# Accelerometer.net
KiCad netlist of a schematic drawn in Altium Designer
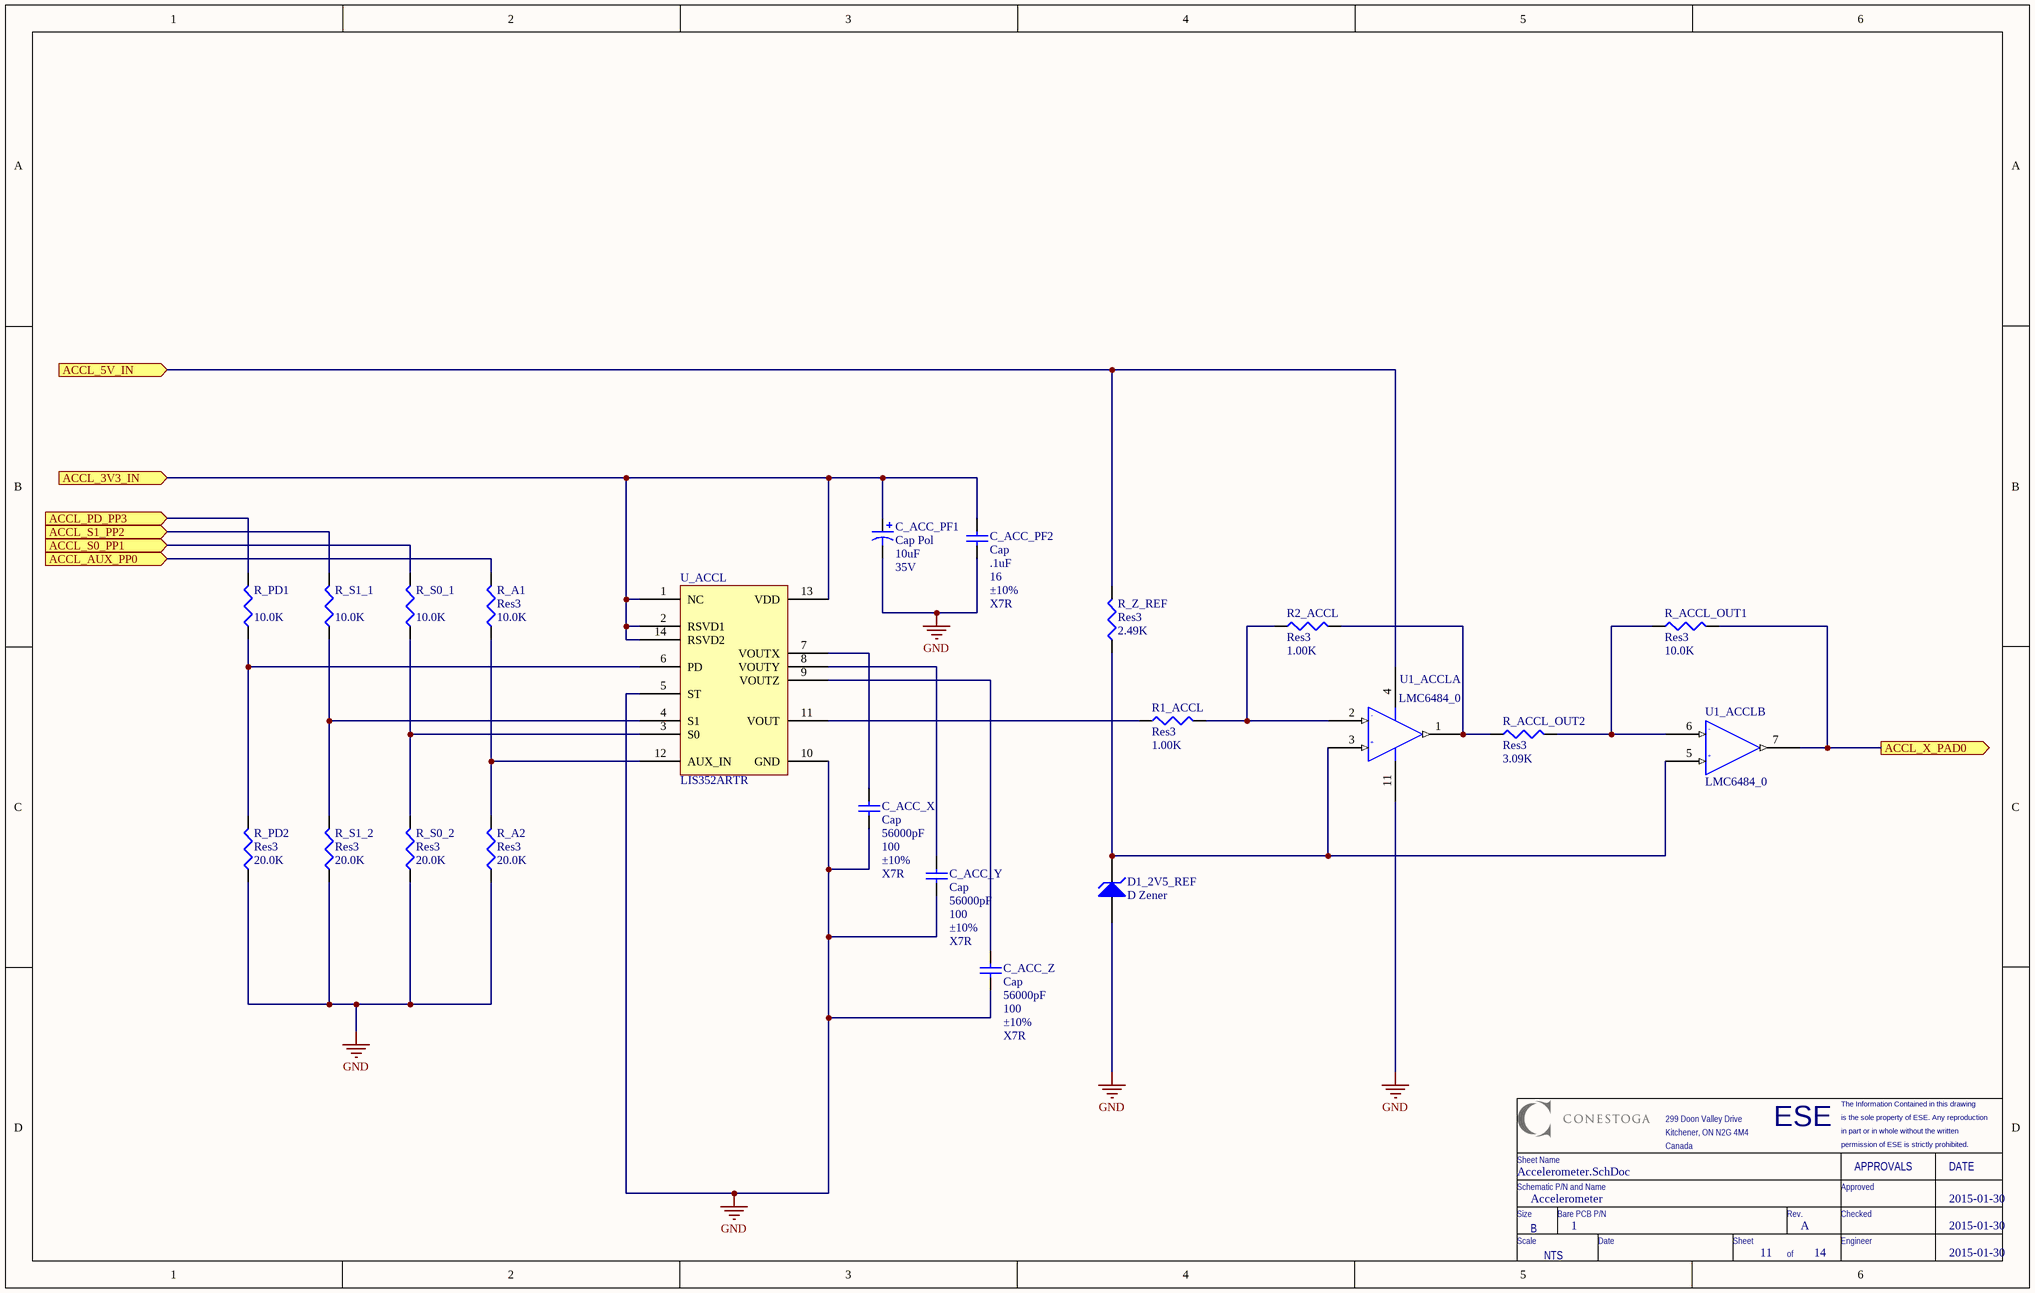
[diagram p0: Accelerometer.SchDoc]

(export (version "E")
  (design (tool "Eeschema 10.0.6"))
  (components
    (comp (ref "C_ACC_PF1")
      (value "Cap Pol")
      (footprint "CAPACITOR_5MM")
      (description "CAP 85C 10uF ±20% 35V WX Series Aluminum Electrolytic")
      (fields
        (field (name "ALTIUM_VALUE") "10uF")
        (field (name "VOLTAGE") "35V")
        (field (name "MPN") "UWX1V100MCL1GB")
      )
      (libsource (lib "esd_library") (part "Cap Polar-10uF-35V"))
    )
    (comp (ref "C_ACC_PF2")
      (value "Cap")
      (footprint "CAPC2012X09M")
      (description "CAP CER .1uF 16v X7R 0805")
      (fields
        (field (name "ALTIUM_VALUE") ".1uF")
        (field (name "WV") "16")
        (field (name "TOLERANCE") "±10%")
        (field (name "TYPE") "X7R")
        (field (name "MPN") "C0805C104K4RACTU")
      )
      (libsource (lib "esd_library") (part "CAP-X7R-.1uF-16V-±10%"))
    )
    (comp (ref "C_ACC_X")
      (value "Cap")
      (footprint "CAPC2012X09M")
      (description "CAP CER 56000pF 100v X7R 0805")
      (fields
        (field (name "ALTIUM_VALUE") "56000pF")
        (field (name "WV") "100")
        (field (name "TOLERANCE") "±10%")
        (field (name "TYPE") "X7R")
        (field (name "MPN") "C0805C563K1RACTU")
      )
      (libsource (lib "esd_library") (part "CAP-X7R-56000pF-100V-±10%"))
    )
    (comp (ref "C_ACC_Y")
      (value "Cap")
      (footprint "CAPC2012X09M")
      (description "CAP CER 56000pF 100v X7R 0805")
      (fields
        (field (name "ALTIUM_VALUE") "56000pF")
        (field (name "WV") "100")
        (field (name "TOLERANCE") "±10%")
        (field (name "TYPE") "X7R")
        (field (name "MPN") "C0805C563K1RACTU")
      )
      (libsource (lib "esd_library") (part "CAP-X7R-56000pF-100V-±10%"))
    )
    (comp (ref "C_ACC_Z")
      (value "Cap")
      (footprint "CAPC2012X09M")
      (description "CAP CER 56000pF 100v X7R 0805")
      (fields
        (field (name "ALTIUM_VALUE") "56000pF")
        (field (name "WV") "100")
        (field (name "TOLERANCE") "±10%")
        (field (name "TYPE") "X7R")
        (field (name "MPN") "C0805C563K1RACTU")
      )
      (libsource (lib "esd_library") (part "CAP-X7R-56000pF-100V-±10%"))
    )
    (comp (ref "D1_2V5_REF")
      (value "D Zener")
      (description "Zener Diode")
      (libsource (lib "Miscellaneous Devices") (part "D Zener"))
    )
    (comp (ref "R1_ACCL")
      (value "Res3")
      (footprint "RESC2112X05M")
      (description "RES SMD 1.00K OHM 1% 1/8W 0805")
      (fields (field (name "ALTIUM_VALUE") "1.00K") (field (name "MPN") "CRCW08051K00FKEA"))
      (libsource (lib "esd_library") (part "Resistor_1.00K"))
    )
    (comp (ref "R2_ACCL")
      (value "Res3")
      (footprint "RESC2112X05M")
      (description "RES SMD 1.00K OHM 1% 1/8W 0805")
      (fields (field (name "ALTIUM_VALUE") "1.00K") (field (name "MPN") "CRCW08051K00FKEA"))
      (libsource (lib "esd_library") (part "Resistor_1.00K"))
    )
    (comp (ref "R_A1")
      (value "Res3")
      (footprint "RESC2112X05M")
      (description "RES SMD 10.0K OHM 1% 1/8W 0805")
      (fields (field (name "ALTIUM_VALUE") "10.0K") (field (name "MPN") "CRCW080510K0FKEA"))
      (libsource (lib "esd_library") (part "Resistor_10.0K"))
    )
    (comp (ref "R_A2")
      (value "Res3")
      (footprint "RESC2112X05M")
      (description "RES SMD 20.0K OHM 1% 1/8W 0805")
      (fields (field (name "ALTIUM_VALUE") "20.0K") (field (name "MPN") "CRCW080520K0FKEA"))
      (libsource (lib "esd_library") (part "Resistor_20.0K"))
    )
    (comp (ref "R_ACCL_OUT1")
      (value "Res3")
      (footprint "RESC2112X05M")
      (description "RES SMD 10.0K OHM 1% 1/8W 0805")
      (fields (field (name "ALTIUM_VALUE") "10.0K") (field (name "MPN") "CRCW080510K0FKEA"))
      (libsource (lib "esd_library") (part "Resistor_10.0K"))
    )
    (comp (ref "R_ACCL_OUT2")
      (value "Res3")
      (footprint "RESC2112X05M")
      (description "RES SMD 3.09K OHM 1% 1/8W 0805")
      (fields (field (name "ALTIUM_VALUE") "3.09K") (field (name "MPN") "CRCW08053K09FKEA"))
      (libsource (lib "esd_library") (part "Resistor_3.09K"))
    )
    (comp (ref "R_PD1")
      (value "10.0K")
      (footprint "RESC2112X05M")
      (description "RES SMD 10.0K OHM 1% 1/8W 0805")
      (fields (field (name "MPN") "CRCW080510K0FKEA") (field (name "Comment") "Res3"))
      (libsource (lib "esd_library") (part "Resistor_10.0K"))
    )
    (comp (ref "R_PD2")
      (value "Res3")
      (footprint "RESC2112X05M")
      (description "RES SMD 20.0K OHM 1% 1/8W 0805")
      (fields (field (name "ALTIUM_VALUE") "20.0K") (field (name "MPN") "CRCW080520K0FKEA"))
      (libsource (lib "esd_library") (part "Resistor_20.0K"))
    )
    (comp (ref "R_S0_1")
      (value "10.0K")
      (footprint "RESC2112X05M")
      (description "RES SMD 10.0K OHM 1% 1/8W 0805")
      (fields (field (name "MPN") "CRCW080510K0FKEA") (field (name "Comment") "Res3"))
      (libsource (lib "esd_library") (part "Resistor_10.0K"))
    )
    (comp (ref "R_S0_2")
      (value "Res3")
      (footprint "RESC2112X05M")
      (description "RES SMD 20.0K OHM 1% 1/8W 0805")
      (fields (field (name "ALTIUM_VALUE") "20.0K") (field (name "MPN") "CRCW080520K0FKEA"))
      (libsource (lib "esd_library") (part "Resistor_20.0K"))
    )
    (comp (ref "R_S1_1")
      (value "10.0K")
      (footprint "RESC2112X05M")
      (description "RES SMD 10.0K OHM 1% 1/8W 0805")
      (fields (field (name "MPN") "CRCW080510K0FKEA") (field (name "Comment") "Res3"))
      (libsource (lib "esd_library") (part "Resistor_10.0K"))
    )
    (comp (ref "R_S1_2")
      (value "Res3")
      (footprint "RESC2112X05M")
      (description "RES SMD 20.0K OHM 1% 1/8W 0805")
      (fields (field (name "ALTIUM_VALUE") "20.0K") (field (name "MPN") "CRCW080520K0FKEA"))
      (libsource (lib "esd_library") (part "Resistor_20.0K"))
    )
    (comp (ref "R_Z_REF")
      (value "Res3")
      (footprint "RESC2112X05M")
      (description "RES SMD 2.49K OHM 1% 1/8W 0805")
      (fields (field (name "ALTIUM_VALUE") "2.49K") (field (name "MPN") "CRCW08052K49FKEA"))
      (libsource (lib "esd_library") (part "Resistor_2.49K"))
    )
    (comp (ref "U1_ACCL")
      (value "LMC6484_0")
      (footprint "SOIC127P600X175-14M-NS")
      (description "IC OPAMP GP 1.5MHZ RRO 14SOIC")
      (fields (field (name "MPN") "LMC6484IMX/NOPB"))
      (libsource (lib "esd_library") (part "LMC6484_0"))
    )
    (comp (ref "U_ACCL")
      (value "LIS352ARTR")
      (footprint "LGA-14-3X5MM")
      (description "IC ACCELEROMETER 3AXIS LP 14LGA")
      (libsource (lib "esd_library") (part "LIS352AR"))
    )
  )
  (nets
    (net (code "1") (name "/ACCL_3V3_IN") (class "Default")
      (node (ref "C_ACC_PF1") (pin "1") (pinfunction "1_1") (pintype "passive"))
      (node (ref "C_ACC_PF2") (pin "2") (pinfunction "2_2") (pintype "passive"))
      (node (ref "U_ACCL") (pin "1") (pinfunction "NC_1") (pintype "passive"))
      (node (ref "U_ACCL") (pin "13") (pinfunction "VDD_13") (pintype "passive"))
      (node (ref "U_ACCL") (pin "14") (pinfunction "RSVD2_14") (pintype "passive"))
      (node (ref "U_ACCL") (pin "2") (pinfunction "RSVD1_2") (pintype "passive"))
    )
    (net (code "2") (name "/ACCL_5V_IN") (class "Default")
      (node (ref "R_Z_REF") (pin "2") (pinfunction "2_2") (pintype "passive"))
      (node (ref "U1_ACCL") (pin "4") (pinfunction "VCC_4") (pintype "power_in"))
    )
    (net (code "3") (name "/ACCL_AUX_PP0") (class "Default")
      (node (ref "R_A1") (pin "2") (pinfunction "2_2") (pintype "passive"))
    )
    (net (code "4") (name "/ACCL_PD_PP3") (class "Default")
      (node (ref "R_PD1") (pin "2") (pinfunction "2_2") (pintype "passive"))
    )
    (net (code "5") (name "/ACCL_S0_PP1") (class "Default")
      (node (ref "R_S0_1") (pin "2") (pinfunction "2_2") (pintype "passive"))
    )
    (net (code "6") (name "/ACCL_S1_PP2") (class "Default")
      (node (ref "R_S1_1") (pin "2") (pinfunction "2_2") (pintype "passive"))
    )
    (net (code "7") (name "/ACCL_X_PAD0") (class "Default")
      (node (ref "R_ACCL_OUT1") (pin "2") (pinfunction "2_2") (pintype "passive"))
      (node (ref "U1_ACCL") (pin "7") (pinfunction "OUT2_7") (pintype "output"))
    )
    (net (code "8") (name "GND") (class "Default")
      (node (ref "C_ACC_PF1") (pin "2") (pinfunction "2_2") (pintype "passive"))
      (node (ref "C_ACC_PF2") (pin "1") (pinfunction "1_1") (pintype "passive"))
      (node (ref "C_ACC_X") (pin "1") (pinfunction "1_1") (pintype "passive"))
      (node (ref "C_ACC_Y") (pin "1") (pinfunction "1_1") (pintype "passive"))
      (node (ref "C_ACC_Z") (pin "1") (pinfunction "1_1") (pintype "passive"))
      (node (ref "D1_2V5_REF") (pin "1") (pinfunction "A_1") (pintype "passive"))
      (node (ref "R_A2") (pin "1") (pinfunction "1_1") (pintype "passive"))
      (node (ref "R_PD2") (pin "1") (pinfunction "1_1") (pintype "passive"))
      (node (ref "R_S0_2") (pin "1") (pinfunction "1_1") (pintype "passive"))
      (node (ref "R_S1_2") (pin "1") (pinfunction "1_1") (pintype "passive"))
      (node (ref "U1_ACCL") (pin "11") (pinfunction "-VCC_11") (pintype "power_in"))
      (node (ref "U_ACCL") (pin "10") (pinfunction "GND_10") (pintype "passive"))
      (node (ref "U_ACCL") (pin "5") (pinfunction "ST_5") (pintype "passive"))
    )
    (net (code "9") (name "Net-(D1_2V5_REF-K)") (class "Default")
      (node (ref "D1_2V5_REF") (pin "2") (pinfunction "K_2") (pintype "passive"))
      (node (ref "R_Z_REF") (pin "1") (pinfunction "1_1") (pintype "passive"))
      (node (ref "U1_ACCL") (pin "3") (pinfunction "NINVIN_1_3") (pintype "input"))
      (node (ref "U1_ACCL") (pin "5") (pinfunction "NINVIN2_5") (pintype "input"))
    )
    (net (code "10") (name "Net-(U1_ACCLA-INVIN_1)") (class "Default")
      (node (ref "R1_ACCL") (pin "2") (pinfunction "2_2") (pintype "passive"))
      (node (ref "R2_ACCL") (pin "1") (pinfunction "1_1") (pintype "passive"))
      (node (ref "U1_ACCL") (pin "2") (pinfunction "INVIN_1_2") (pintype "input"))
    )
    (net (code "11") (name "Net-(U1_ACCLA-OUT1)") (class "Default")
      (node (ref "R2_ACCL") (pin "2") (pinfunction "2_2") (pintype "passive"))
      (node (ref "R_ACCL_OUT2") (pin "1") (pinfunction "1_1") (pintype "passive"))
      (node (ref "U1_ACCL") (pin "1") (pinfunction "OUT1_1") (pintype "output"))
    )
    (net (code "12") (name "Net-(U1_ACCLB-INVIN2)") (class "Default")
      (node (ref "R_ACCL_OUT1") (pin "1") (pinfunction "1_1") (pintype "passive"))
      (node (ref "R_ACCL_OUT2") (pin "2") (pinfunction "2_2") (pintype "passive"))
      (node (ref "U1_ACCL") (pin "6") (pinfunction "INVIN2_6") (pintype "input"))
    )
    (net (code "13") (name "Net-(U_ACCL-AUX_IN)") (class "Default")
      (node (ref "R_A1") (pin "1") (pinfunction "1_1") (pintype "passive"))
      (node (ref "R_A2") (pin "2") (pinfunction "2_2") (pintype "passive"))
      (node (ref "U_ACCL") (pin "12") (pinfunction "AUX_IN_12") (pintype "passive"))
    )
    (net (code "14") (name "Net-(U_ACCL-PD)") (class "Default")
      (node (ref "R_PD1") (pin "1") (pinfunction "1_1") (pintype "passive"))
      (node (ref "R_PD2") (pin "2") (pinfunction "2_2") (pintype "passive"))
      (node (ref "U_ACCL") (pin "6") (pinfunction "PD_6") (pintype "passive"))
    )
    (net (code "15") (name "Net-(U_ACCL-S0)") (class "Default")
      (node (ref "R_S0_1") (pin "1") (pinfunction "1_1") (pintype "passive"))
      (node (ref "R_S0_2") (pin "2") (pinfunction "2_2") (pintype "passive"))
      (node (ref "U_ACCL") (pin "3") (pinfunction "S0_3") (pintype "passive"))
    )
    (net (code "16") (name "Net-(U_ACCL-S1)") (class "Default")
      (node (ref "R_S1_1") (pin "1") (pinfunction "1_1") (pintype "passive"))
      (node (ref "R_S1_2") (pin "2") (pinfunction "2_2") (pintype "passive"))
      (node (ref "U_ACCL") (pin "4") (pinfunction "S1_4") (pintype "passive"))
    )
    (net (code "17") (name "Net-(U_ACCL-VOUT)") (class "Default")
      (node (ref "R1_ACCL") (pin "1") (pinfunction "1_1") (pintype "passive"))
      (node (ref "U_ACCL") (pin "11") (pinfunction "VOUT_11") (pintype "passive"))
    )
    (net (code "18") (name "Net-(U_ACCL-VOUTX)") (class "Default")
      (node (ref "C_ACC_X") (pin "2") (pinfunction "2_2") (pintype "passive"))
      (node (ref "U_ACCL") (pin "7") (pinfunction "VOUTX_7") (pintype "passive"))
    )
    (net (code "19") (name "Net-(U_ACCL-VOUTY)") (class "Default")
      (node (ref "C_ACC_Y") (pin "2") (pinfunction "2_2") (pintype "passive"))
      (node (ref "U_ACCL") (pin "8") (pinfunction "VOUTY_8") (pintype "passive"))
    )
    (net (code "20") (name "Net-(U_ACCL-VOUTZ)") (class "Default")
      (node (ref "C_ACC_Z") (pin "2") (pinfunction "2_2") (pintype "passive"))
      (node (ref "U_ACCL") (pin "9") (pinfunction "VOUTZ_9") (pintype "passive"))
    )
  )
)
